# GPS_Tracker.net
KiCad netlist of a schematic drawn in EAGLE
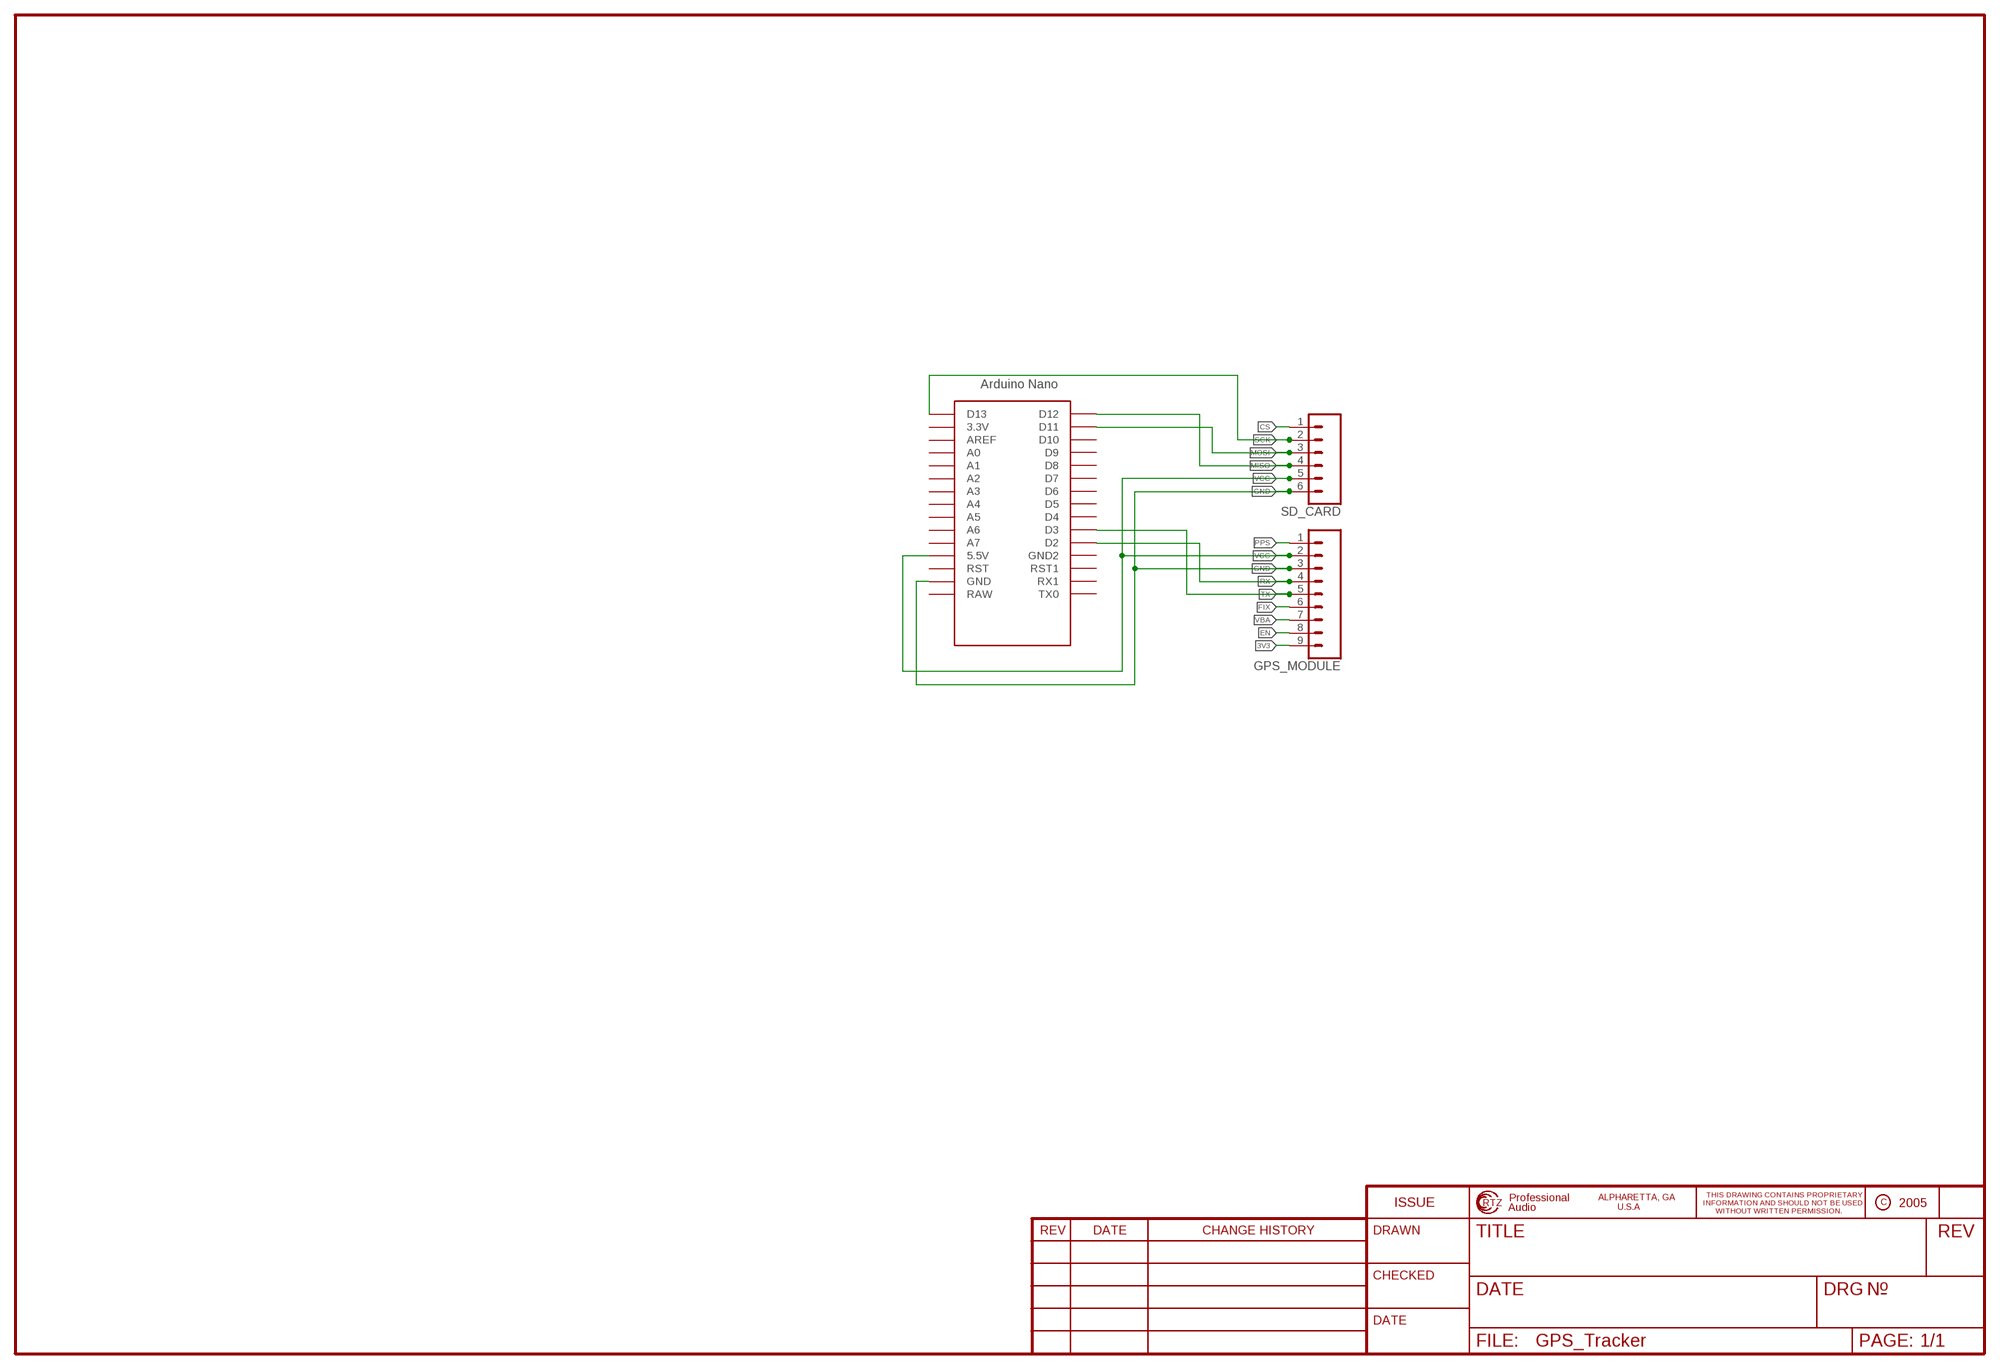
[diagram p0: schematic, sheet 1]

(export (version "E")
  (design (tool "Eeschema 10.0.6"))
  (components
    (comp (ref "GPS_MODULE")
      (value "CONN_09")
      (footprint "eagle-import:1X09")
      (libsource (lib "eagle-import") (part "CONN_09"))
    )
    (comp (ref "SD_CARD")
      (value "CONN_06SILK_FEMALE_PTH")
      (footprint "eagle-import:1X06")
      (libsource (lib "eagle-import") (part "CONN_06SILK_FEMALE_PTH"))
    )
    (comp (ref "U$1")
      (value "NANO")
      (footprint "eagle-import:NANO")
      (libsource (lib "eagle-import") (part "NANO"))
    )
  )
  (nets
    (net (code "1") (name "3V3") (class "Default")
      (node (ref "GPS_MODULE") (pin "9") (pinfunction "9_9") (pintype "passive"))
    )
    (net (code "2") (name "CS") (class "Default")
      (node (ref "SD_CARD") (pin "1") (pinfunction "1_1") (pintype "passive"))
    )
    (net (code "3") (name "EN") (class "Default")
      (node (ref "GPS_MODULE") (pin "8") (pinfunction "8_8") (pintype "passive"))
    )
    (net (code "4") (name "FIX") (class "Default")
      (node (ref "GPS_MODULE") (pin "6") (pinfunction "6_6") (pintype "passive"))
    )
    (net (code "5") (name "GND") (class "Default")
      (node (ref "GPS_MODULE") (pin "3") (pinfunction "3_3") (pintype "passive"))
      (node (ref "SD_CARD") (pin "6") (pinfunction "6_6") (pintype "passive"))
      (node (ref "U$1") (pin "GND") (pinfunction "GND_GND") (pintype "bidirectional"))
    )
    (net (code "6") (name "MISO") (class "Default")
      (node (ref "SD_CARD") (pin "4") (pinfunction "4_4") (pintype "passive"))
      (node (ref "U$1") (pin "D12") (pinfunction "D12_D12") (pintype "bidirectional"))
    )
    (net (code "7") (name "MOSI") (class "Default")
      (node (ref "SD_CARD") (pin "3") (pinfunction "3_3") (pintype "passive"))
      (node (ref "U$1") (pin "D11") (pinfunction "D11_D11") (pintype "bidirectional"))
    )
    (net (code "8") (name "PPS") (class "Default")
      (node (ref "GPS_MODULE") (pin "1") (pinfunction "1_1") (pintype "passive"))
    )
    (net (code "9") (name "RX") (class "Default")
      (node (ref "GPS_MODULE") (pin "4") (pinfunction "4_4") (pintype "passive"))
      (node (ref "U$1") (pin "D2") (pinfunction "D2_D2") (pintype "bidirectional"))
    )
    (net (code "10") (name "SCK") (class "Default")
      (node (ref "SD_CARD") (pin "2") (pinfunction "2_2") (pintype "passive"))
      (node (ref "U$1") (pin "D13") (pinfunction "D13_D13") (pintype "bidirectional"))
    )
    (net (code "11") (name "TX") (class "Default")
      (node (ref "GPS_MODULE") (pin "5") (pinfunction "5_5") (pintype "passive"))
      (node (ref "U$1") (pin "D3") (pinfunction "D3_D3") (pintype "bidirectional"))
    )
    (net (code "12") (name "VBA") (class "Default")
      (node (ref "GPS_MODULE") (pin "7") (pinfunction "7_7") (pintype "passive"))
    )
    (net (code "13") (name "VCC") (class "Default")
      (node (ref "GPS_MODULE") (pin "2") (pinfunction "2_2") (pintype "passive"))
      (node (ref "SD_CARD") (pin "5") (pinfunction "5_5") (pintype "passive"))
      (node (ref "U$1") (pin "5V") (pinfunction "5.5V_5V") (pintype "bidirectional"))
    )
    (net (code "14") (name "unconnected-(U$1-GND2-PadGND1)") (class "Default")
      (node (ref "U$1") (pin "GND1") (pinfunction "GND2_GND1") (pintype "bidirectional"))
    )
    (net (code "15") (name "unconnected-(U$1-Pad3.3V)") (class "Default")
      (node (ref "U$1") (pin "3.3V") (pinfunction "3.3V_3.3V") (pintype "bidirectional"))
    )
    (net (code "16") (name "unconnected-(U$1-PadA0)") (class "Default")
      (node (ref "U$1") (pin "A0") (pinfunction "A0_A0") (pintype "bidirectional"))
    )
    (net (code "17") (name "unconnected-(U$1-PadA1)") (class "Default")
      (node (ref "U$1") (pin "A1") (pinfunction "A1_A1") (pintype "bidirectional"))
    )
    (net (code "18") (name "unconnected-(U$1-PadA2)") (class "Default")
      (node (ref "U$1") (pin "A2") (pinfunction "A2_A2") (pintype "bidirectional"))
    )
    (net (code "19") (name "unconnected-(U$1-PadA3)") (class "Default")
      (node (ref "U$1") (pin "A3") (pinfunction "A3_A3") (pintype "bidirectional"))
    )
    (net (code "20") (name "unconnected-(U$1-PadA4)") (class "Default")
      (node (ref "U$1") (pin "A4") (pinfunction "A4_A4") (pintype "bidirectional"))
    )
    (net (code "21") (name "unconnected-(U$1-PadA5)") (class "Default")
      (node (ref "U$1") (pin "A5") (pinfunction "A5_A5") (pintype "bidirectional"))
    )
    (net (code "22") (name "unconnected-(U$1-PadA6)") (class "Default")
      (node (ref "U$1") (pin "A6") (pinfunction "A6_A6") (pintype "bidirectional"))
    )
    (net (code "23") (name "unconnected-(U$1-PadA7)") (class "Default")
      (node (ref "U$1") (pin "A7") (pinfunction "A7_A7") (pintype "bidirectional"))
    )
    (net (code "24") (name "unconnected-(U$1-PadAREF)") (class "Default")
      (node (ref "U$1") (pin "AREF") (pinfunction "AREF_AREF") (pintype "bidirectional"))
    )
    (net (code "25") (name "unconnected-(U$1-PadD4)") (class "Default")
      (node (ref "U$1") (pin "D4") (pinfunction "D4_D4") (pintype "bidirectional"))
    )
    (net (code "26") (name "unconnected-(U$1-PadD5)") (class "Default")
      (node (ref "U$1") (pin "D5") (pinfunction "D5_D5") (pintype "bidirectional"))
    )
    (net (code "27") (name "unconnected-(U$1-PadD6)") (class "Default")
      (node (ref "U$1") (pin "D6") (pinfunction "D6_D6") (pintype "bidirectional"))
    )
    (net (code "28") (name "unconnected-(U$1-PadD7)") (class "Default")
      (node (ref "U$1") (pin "D7") (pinfunction "D7_D7") (pintype "bidirectional"))
    )
    (net (code "29") (name "unconnected-(U$1-PadD8)") (class "Default")
      (node (ref "U$1") (pin "D8") (pinfunction "D8_D8") (pintype "bidirectional"))
    )
    (net (code "30") (name "unconnected-(U$1-PadD9)") (class "Default")
      (node (ref "U$1") (pin "D9") (pinfunction "D9_D9") (pintype "bidirectional"))
    )
    (net (code "31") (name "unconnected-(U$1-PadD10)") (class "Default")
      (node (ref "U$1") (pin "D10") (pinfunction "D10_D10") (pintype "bidirectional"))
    )
    (net (code "32") (name "unconnected-(U$1-PadICSP1)") (class "Default")
      (node (ref "U$1") (pin "ICSP1") (pinfunction "ICSP1_ICSP1") (pintype "bidirectional"))
    )
    (net (code "33") (name "unconnected-(U$1-PadICSP2)") (class "Default")
      (node (ref "U$1") (pin "ICSP2") (pinfunction "ICSP2_ICSP2") (pintype "bidirectional"))
    )
    (net (code "34") (name "unconnected-(U$1-PadICSP3)") (class "Default")
      (node (ref "U$1") (pin "ICSP3") (pinfunction "ICSP3_ICSP3") (pintype "bidirectional"))
    )
    (net (code "35") (name "unconnected-(U$1-PadICSP4)") (class "Default")
      (node (ref "U$1") (pin "ICSP4") (pinfunction "ICSP4_ICSP4") (pintype "bidirectional"))
    )
    (net (code "36") (name "unconnected-(U$1-PadICSP5)") (class "Default")
      (node (ref "U$1") (pin "ICSP5") (pinfunction "ICSP5_ICSP5") (pintype "bidirectional"))
    )
    (net (code "37") (name "unconnected-(U$1-PadICSP6)") (class "Default")
      (node (ref "U$1") (pin "ICSP6") (pinfunction "ICSP6_ICSP6") (pintype "bidirectional"))
    )
    (net (code "38") (name "unconnected-(U$1-PadRAW)") (class "Default")
      (node (ref "U$1") (pin "RAW") (pinfunction "RAW_RAW") (pintype "bidirectional"))
    )
    (net (code "39") (name "unconnected-(U$1-PadRST)") (class "Default")
      (node (ref "U$1") (pin "RST") (pinfunction "RST_RST") (pintype "bidirectional"))
    )
    (net (code "40") (name "unconnected-(U$1-PadRST1)") (class "Default")
      (node (ref "U$1") (pin "RST1") (pinfunction "RST1_RST1") (pintype "bidirectional"))
    )
    (net (code "41") (name "unconnected-(U$1-PadRX1)") (class "Default")
      (node (ref "U$1") (pin "RX1") (pinfunction "RX1_RX1") (pintype "bidirectional"))
    )
    (net (code "42") (name "unconnected-(U$1-PadTX0)") (class "Default")
      (node (ref "U$1") (pin "TX0") (pinfunction "TX0_TX0") (pintype "bidirectional"))
    )
  )
)
